# CLK_INPUT.net
KiCad netlist of a schematic drawn in Altium Designer
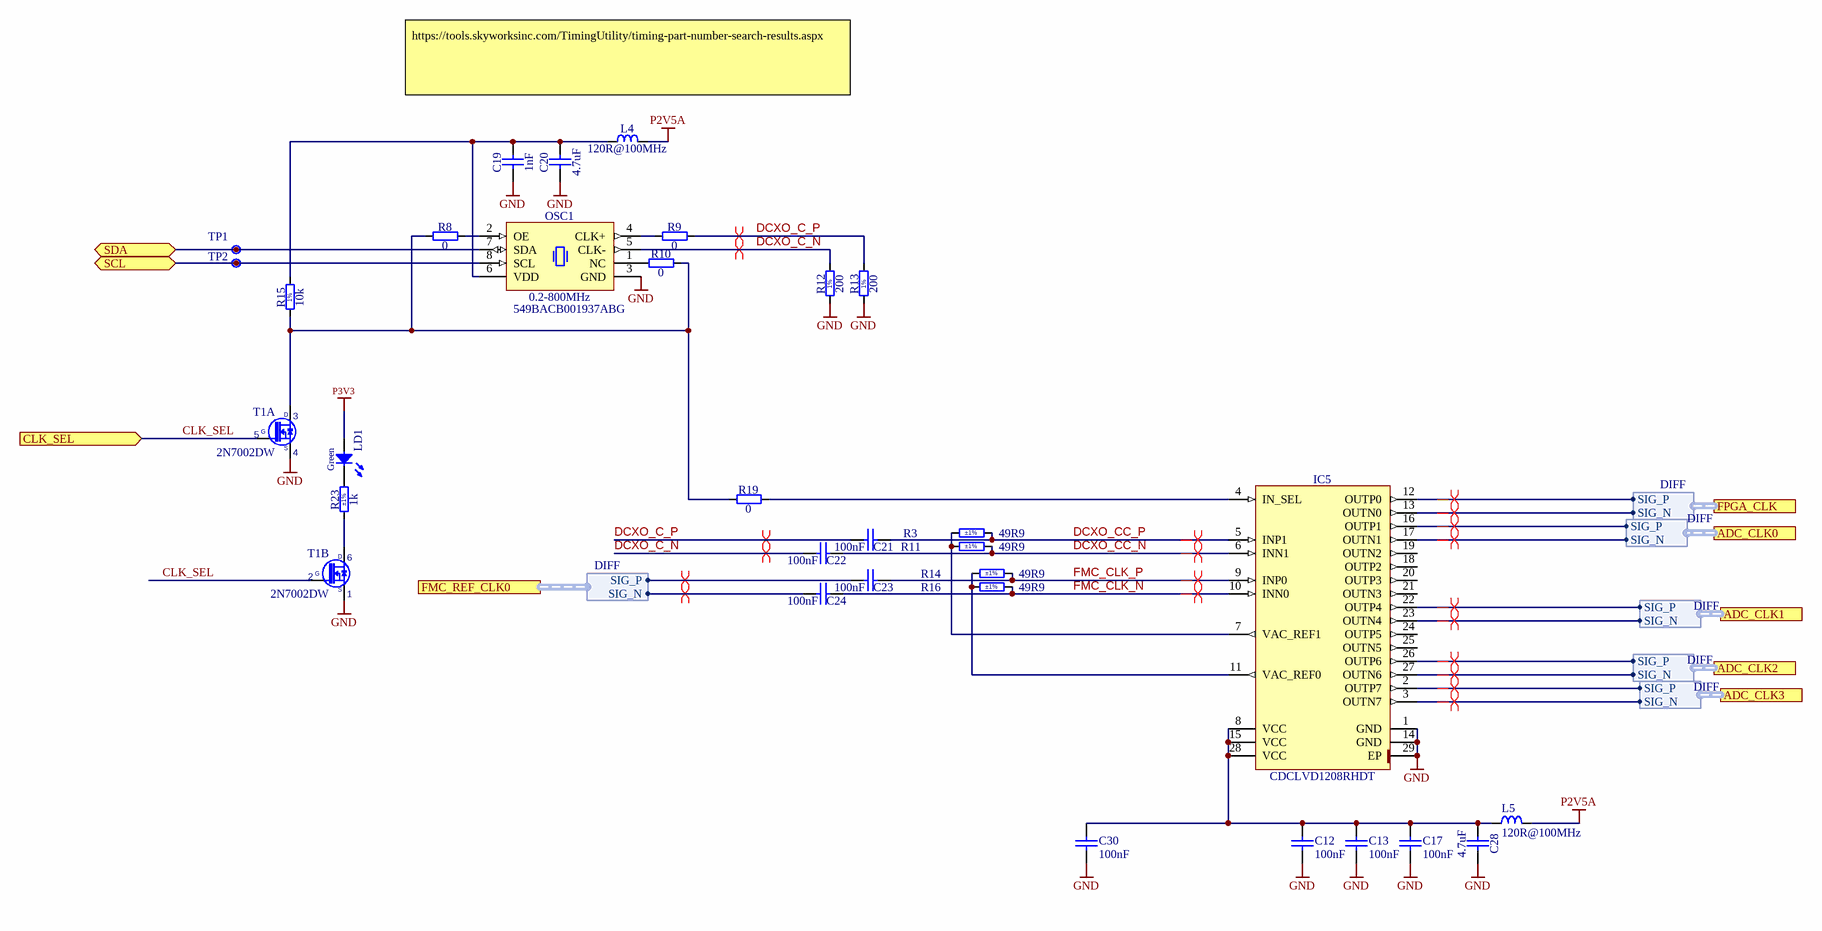
[diagram p0: CLK_INPUT.SchDoc]

(export (version "E")
  (design (tool "Eeschema 10.0.6"))
  (components
    (comp (ref "C12")
      (value "100nF")
      (footprint "CAPC0603X33N")
      (description "Non-polarised capacitor")
      (fields
        (field (name "PART NUMBER") "CC0201_100NF_6.3V_10%_X5R")
        (field (name "VOLTAGE") "6.3V")
        (field (name "AUTHOR") "CERN DEM JLC")
      )
      (libsource (lib "Capacitors") (part "Capacitor - non polarized"))
    )
    (comp (ref "C13")
      (value "100nF")
      (footprint "CAPC0603X33N")
      (description "Non-polarised capacitor")
      (fields
        (field (name "PART NUMBER") "CC0201_100NF_6.3V_10%_X5R")
        (field (name "VOLTAGE") "6.3V")
        (field (name "AUTHOR") "CERN DEM JLC")
      )
      (libsource (lib "Capacitors") (part "Capacitor - non polarized"))
    )
    (comp (ref "C17")
      (value "100nF")
      (footprint "CAPC0603X33N")
      (description "Non-polarised capacitor")
      (fields
        (field (name "PART NUMBER") "CC0201_100NF_6.3V_10%_X5R")
        (field (name "VOLTAGE") "6.3V")
        (field (name "AUTHOR") "CERN DEM JLC")
      )
      (libsource (lib "Capacitors") (part "Capacitor - non polarized"))
    )
    (comp (ref "C19")
      (value "1nF")
      (footprint "CAPC1005X55N")
      (description "Non-polarised capacitor")
      (fields
        (field (name "PART NUMBER") "CC0402_1NF_50V_10%_X7R")
        (field (name "VOLTAGE") "50V")
        (field (name "AUTHOR") "CERN DEM JLC")
      )
      (libsource (lib "Capacitors") (part "Capacitor - non polarized"))
    )
    (comp (ref "C20")
      (value "4.7uF")
      (footprint "CAPC2012X135N")
      (description "Non-polarised capacitor")
      (fields
        (field (name "PART NUMBER") "CC0805_4.7UF_10V_10%_X5R")
        (field (name "VOLTAGE") "10V")
        (field (name "AUTHOR") "CERN DEM JLC")
      )
      (libsource (lib "Capacitors") (part "Capacitor - non polarized"))
    )
    (comp (ref "C21")
      (value "100nF")
      (footprint "CAPC0603X33N")
      (description "Non-polarised capacitor")
      (fields
        (field (name "PART NUMBER") "CC0201_100NF_6.3V_10%_X5R")
        (field (name "VOLTAGE") "6.3V")
        (field (name "AUTHOR") "CERN DEM JLC")
      )
      (libsource (lib "Capacitors") (part "Capacitor - non polarized"))
    )
    (comp (ref "C22")
      (value "100nF")
      (footprint "CAPC0603X33N")
      (description "Non-polarised capacitor")
      (fields
        (field (name "PART NUMBER") "CC0201_100NF_6.3V_10%_X5R")
        (field (name "VOLTAGE") "6.3V")
        (field (name "AUTHOR") "CERN DEM JLC")
      )
      (libsource (lib "Capacitors") (part "Capacitor - non polarized"))
    )
    (comp (ref "C23")
      (value "100nF")
      (footprint "CAPC0603X33N")
      (description "Non-polarised capacitor")
      (fields
        (field (name "PART NUMBER") "CC0201_100NF_6.3V_10%_X5R")
        (field (name "VOLTAGE") "6.3V")
        (field (name "AUTHOR") "CERN DEM JLC")
      )
      (libsource (lib "Capacitors") (part "Capacitor - non polarized"))
    )
    (comp (ref "C24")
      (value "100nF")
      (footprint "CAPC0603X33N")
      (description "Non-polarised capacitor")
      (fields
        (field (name "PART NUMBER") "CC0201_100NF_6.3V_10%_X5R")
        (field (name "VOLTAGE") "6.3V")
        (field (name "AUTHOR") "CERN DEM JLC")
      )
      (libsource (lib "Capacitors") (part "Capacitor - non polarized"))
    )
    (comp (ref "C28")
      (value "4.7uF")
      (footprint "CAPC2012X135N")
      (description "Non-polarised capacitor")
      (fields
        (field (name "PART NUMBER") "CC0805_4.7UF_10V_10%_X5R")
        (field (name "VOLTAGE") "10V")
        (field (name "AUTHOR") "CERN DEM JLC")
      )
      (libsource (lib "Capacitors") (part "Capacitor - non polarized"))
    )
    (comp (ref "C30")
      (value "100nF")
      (footprint "CAPC0603X33N")
      (description "Non-polarised capacitor")
      (fields
        (field (name "PART NUMBER") "CC0201_100NF_6.3V_10%_X5R")
        (field (name "VOLTAGE") "6.3V")
        (field (name "AUTHOR") "CERN DEM JLC")
      )
      (libsource (lib "Capacitors") (part "Capacitor - non polarized"))
    )
    (comp (ref "IC5")
      (value "CDCLVD1208RHDT")
      (footprint "QFN50P500X500X100-29N-S325")
      (description "2:8 Low Additive Jitter LVDS Buffer")
      (fields (field (name "MANUFACTURER") "TEXAS INSTRUMENTS") (field (name "AUTHOR") "CERN DEM JLC"))
      (libsource (lib "ICs And Semiconductors") (part "CDCLVD1208"))
    )
    (comp (ref "L4")
      (value "120R@100MHz")
      (footprint "INDC1608X65N")
      (description "Inductor")
      (fields
        (field (name "PART NUMBER") "IND0603_MURATA_BLM18SG121TN1D")
        (field (name "POWER") "3A")
        (field (name "AUTHOR") "CERN DEM JLC")
      )
      (libsource (lib "") (part "Inductor_1"))
    )
    (comp (ref "L5")
      (value "120R@100MHz")
      (footprint "INDC1608X95N")
      (description "Inductor")
      (fields
        (field (name "PART NUMBER") "IND0603_MURATA_BLM18PG121SN1D")
        (field (name "POWER") "2A")
        (field (name "AUTHOR") "CERN DEM BC")
      )
      (libsource (lib "Inductors & Transformers") (part "Inductor"))
    )
    (comp (ref "LD1")
      (value "Green")
      (footprint "LED_KINGBRIGHT_KPA-1606CGCK")
      (description "LED Green 1C 2A")
      (fields
        (field (name "PART NUMBER") "LED_KINGBRIGHT_KPA-1606CGCK")
        (field (name "MANUFACTURER") "KINGBRIGHT")
        (field (name "AUTHOR") "CERN DEM MR")
      )
      (libsource (lib "ICs And Semiconductors") (part "LED Green 1C 2A"))
    )
    (comp (ref "OSC1")
      (value "0.2-800MHz")
      (footprint "OSC_SILICON-LAB_SI549-A")
      (description "Ultra Low Jitter I2C Programmable Crystal Oscillator (XO), Si549 Series")
      (fields
        (field (name "PART NUMBER") "OSC_0.2-800MHZ_SILICON-LAB_549BACB001937ABG")
        (field (name "MANUFACTURER") "SILICON LABS")
        (field (name "MANUFACTURER PART NUMBER") "549BACB001937ABG")
        (field (name "AUTHOR") "CERN DEM JMW")
      )
      (libsource (lib "ICs And Semiconductors") (part "Oscillator SILICON-LAB_Si549-CD"))
    )
    (comp (ref "R3")
      (value "49R9")
      (footprint "RESC1005X40N")
      (description "Resistor - 1%")
      (fields
        (field (name "TOLERANCE") "±1%")
        (field (name "PART NUMBER") "R0402_49R9_1%_0.0625W_100PPM")
        (field (name "POWER") "0.0625W")
        (field (name "AUTHOR") "CERN DEM JLC")
      )
      (libsource (lib "Resistors") (part "Resistor - 1%"))
    )
    (comp (ref "R8")
      (value "0")
      (footprint "RESC1005X40N")
      (description "Resistor")
      (fields
        (field (name "PART NUMBER") "R0402_0R_JUMPER")
        (field (name "MANUFACTURER") "GENERIC")
        (field (name "AUTHOR") "CERN DEM JLC")
      )
      (libsource (lib "Resistors") (part "Resistor"))
    )
    (comp (ref "R9")
      (value "0")
      (footprint "RESC1005X40N")
      (description "Resistor")
      (fields
        (field (name "PART NUMBER") "R0402_0R_JUMPER")
        (field (name "MANUFACTURER") "GENERIC")
        (field (name "AUTHOR") "CERN DEM JLC")
      )
      (libsource (lib "Resistors") (part "Resistor"))
    )
    (comp (ref "R10")
      (value "0")
      (footprint "RESC1005X40N")
      (description "Resistor")
      (fields
        (field (name "PART NUMBER") "R0402_0R_JUMPER")
        (field (name "MANUFACTURER") "GENERIC")
        (field (name "AUTHOR") "CERN DEM JLC")
      )
      (libsource (lib "Resistors") (part "Resistor"))
    )
    (comp (ref "R11")
      (value "49R9")
      (footprint "RESC1005X40N")
      (description "Resistor - 1%")
      (fields
        (field (name "TOLERANCE") "±1%")
        (field (name "PART NUMBER") "R0402_49R9_1%_0.0625W_100PPM")
        (field (name "POWER") "0.0625W")
        (field (name "AUTHOR") "CERN DEM JLC")
      )
      (libsource (lib "Resistors") (part "Resistor - 1%"))
    )
    (comp (ref "R12")
      (value "200")
      (footprint "RESC1005X40N")
      (description "Resistor - 1%")
      (fields
        (field (name "PART NUMBER") "R0402_200R_1%_0.0625W_100PPM")
        (field (name "POWER") "0.0625W")
        (field (name "AUTHOR") "CERN DEM JLC")
      )
      (libsource (lib "Resistors") (part "Resistor - 1%"))
    )
    (comp (ref "R13")
      (value "200")
      (footprint "RESC1005X40N")
      (description "Resistor - 1%")
      (fields
        (field (name "PART NUMBER") "R0402_200R_1%_0.0625W_100PPM")
        (field (name "POWER") "0.0625W")
        (field (name "AUTHOR") "CERN DEM JLC")
      )
      (libsource (lib "Resistors") (part "Resistor - 1%"))
    )
    (comp (ref "R14")
      (value "49R9")
      (footprint "RESC1005X40N")
      (description "Resistor - 1%")
      (fields
        (field (name "TOLERANCE") "±1%")
        (field (name "PART NUMBER") "R0402_49R9_1%_0.0625W_100PPM")
        (field (name "POWER") "0.0625W")
        (field (name "AUTHOR") "CERN DEM JLC")
      )
      (libsource (lib "Resistors") (part "Resistor - 1%"))
    )
    (comp (ref "R15")
      (value "10k")
      (footprint "RESC1005X40N")
      (description "Resistor - 1%")
      (fields
        (field (name "PART NUMBER") "R0402_10K_1%_0.0625W_100PPM")
        (field (name "POWER") "0.0625W")
        (field (name "AUTHOR") "CERN DEM JLC")
      )
      (libsource (lib "Resistors") (part "Resistor - 1%"))
    )
    (comp (ref "R16")
      (value "49R9")
      (footprint "RESC1005X40N")
      (description "Resistor - 1%")
      (fields
        (field (name "TOLERANCE") "±1%")
        (field (name "PART NUMBER") "R0402_49R9_1%_0.0625W_100PPM")
        (field (name "POWER") "0.0625W")
        (field (name "AUTHOR") "CERN DEM JLC")
      )
      (libsource (lib "Resistors") (part "Resistor - 1%"))
    )
    (comp (ref "R19")
      (value "0")
      (footprint "RESC1005X40N")
      (description "Resistor")
      (fields
        (field (name "PART NUMBER") "R0402_0R_JUMPER")
        (field (name "MANUFACTURER") "GENERIC")
        (field (name "AUTHOR") "CERN DEM JLC")
      )
      (libsource (lib "Resistors") (part "Resistor"))
    )
    (comp (ref "R23")
      (value "1k")
      (footprint "RESC1005X40N")
      (description "Resistor - 1%")
      (fields
        (field (name "TOLERANCE") "±1%")
        (field (name "PART NUMBER") "R0402_1K_1%_0.0625W_100PPM")
        (field (name "POWER") "0.0625W")
        (field (name "AUTHOR") "CERN DEM JLC")
      )
      (libsource (lib "Resistors") (part "Resistor - 1%"))
    )
    (comp (ref "T1")
      (value "2N7002DW")
      (footprint "SOT65P210X110-6N")
      (description "60 V, 115 mA, Dual N-Channel Field Effect Transistor, Enhancement Mode")
      (fields (field (name "MANUFACTURER") "ON SEMICONDUCTOR") (field (name "AUTHOR") "CERN DEM BC"))
      (libsource (lib "ICs And Semiconductors") (part "2N7002DW"))
    )
    (comp (ref "TP1")
      (value "I2C SW SDA")
      (footprint "TPS127")
      (description "Test Point")
      (fields (field (name "PART NUMBER") "SMD_PAD_1.27X1.27MM") (field (name "AUTHOR") "CERN DEM JLC"))
      (libsource (lib "Eletro-mechanical") (part "Test Point"))
    )
    (comp (ref "TP2")
      (value "I2C SW SCL")
      (footprint "TPS127")
      (description "Test Point")
      (fields (field (name "PART NUMBER") "SMD_PAD_1.27X1.27MM") (field (name "AUTHOR") "CERN DEM JLC"))
      (libsource (lib "Eletro-mechanical") (part "Test Point"))
    )
  )
  (nets
    (net (code "2") (name "/CLK_SEL") (class "Default")
      (node (ref "T1") (pin "2") (pinfunction "G2_2") (pintype "passive"))
      (node (ref "T1") (pin "5") (pinfunction "G1_5") (pintype "passive"))
    )
    (net (code "3") (name "/DCXO_CC_N") (class "Default")
      (node (ref "C22") (pin "2") (pinfunction "2_2") (pintype "passive"))
      (node (ref "IC5") (pin "6") (pinfunction "INN1_6") (pintype "input"))
      (node (ref "R11") (pin "2") (pinfunction "2_2") (pintype "passive"))
    )
    (net (code "4") (name "/DCXO_CC_P") (class "Default")
      (node (ref "C21") (pin "2") (pinfunction "2_2") (pintype "passive"))
      (node (ref "IC5") (pin "5") (pinfunction "INP1_5") (pintype "input"))
      (node (ref "R3") (pin "2") (pinfunction "2_2") (pintype "passive"))
    )
    (net (code "5") (name "/DCXO_C_N") (class "Default")
      (node (ref "C22") (pin "1") (pinfunction "1_1") (pintype "passive"))
      (node (ref "OSC1") (pin "5") (pinfunction "CLK-_5") (pintype "output"))
      (node (ref "R12") (pin "2") (pinfunction "2_2") (pintype "passive"))
    )
    (net (code "6") (name "/DCXO_C_P") (class "Default")
      (node (ref "C21") (pin "1") (pinfunction "1_1") (pintype "passive"))
      (node (ref "R13") (pin "2") (pinfunction "2_2") (pintype "passive"))
      (node (ref "R9") (pin "2") (pinfunction "2_2") (pintype "passive"))
    )
    (net (code "7") (name "/FMC_CLK_N") (class "Default")
      (node (ref "C24") (pin "2") (pinfunction "2_2") (pintype "passive"))
      (node (ref "IC5") (pin "10") (pinfunction "INN0_10") (pintype "input"))
      (node (ref "R16") (pin "2") (pinfunction "2_2") (pintype "passive"))
    )
    (net (code "8") (name "/FMC_CLK_P") (class "Default")
      (node (ref "C23") (pin "2") (pinfunction "2_2") (pintype "passive"))
      (node (ref "IC5") (pin "9") (pinfunction "INP0_9") (pintype "input"))
      (node (ref "R14") (pin "2") (pinfunction "2_2") (pintype "passive"))
    )
    (net (code "9") (name "/SCL") (class "Default")
      (node (ref "OSC1") (pin "8") (pinfunction "SCL_8") (pintype "input"))
      (node (ref "TP2") (pin "1") (pinfunction "1_1") (pintype "bidirectional"))
    )
    (net (code "10") (name "/SDA") (class "Default")
      (node (ref "OSC1") (pin "7") (pinfunction "SDA_7") (pintype "bidirectional"))
      (node (ref "TP1") (pin "1") (pinfunction "1_1") (pintype "bidirectional"))
    )
    (net (code "12") (name "GND") (class "Default")
      (node (ref "C12") (pin "1") (pinfunction "1_1") (pintype "passive"))
      (node (ref "C13") (pin "1") (pinfunction "1_1") (pintype "passive"))
      (node (ref "C17") (pin "1") (pinfunction "1_1") (pintype "passive"))
      (node (ref "C19") (pin "1") (pinfunction "1_1") (pintype "passive"))
      (node (ref "C20") (pin "1") (pinfunction "1_1") (pintype "passive"))
      (node (ref "C28") (pin "1") (pinfunction "1_1") (pintype "passive"))
      (node (ref "C30") (pin "1") (pinfunction "1_1") (pintype "passive"))
      (node (ref "IC5") (pin "1") (pinfunction "GND_1") (pintype "power_in"))
      (node (ref "IC5") (pin "14") (pinfunction "GND_14") (pintype "power_in"))
      (node (ref "IC5") (pin "29") (pinfunction "EP_29") (pintype "power_in"))
      (node (ref "OSC1") (pin "3") (pinfunction "GND_3") (pintype "power_in"))
      (node (ref "R12") (pin "1") (pinfunction "1_1") (pintype "passive"))
      (node (ref "R13") (pin "1") (pinfunction "1_1") (pintype "passive"))
      (node (ref "T1") (pin "1") (pinfunction "S2_1") (pintype "passive"))
      (node (ref "T1") (pin "4") (pinfunction "S1_4") (pintype "passive"))
    )
    (net (code "13") (name "Net-(C12-Pad2)") (class "Default")
      (node (ref "C12") (pin "2") (pinfunction "2_2") (pintype "passive"))
      (node (ref "C13") (pin "2") (pinfunction "2_2") (pintype "passive"))
      (node (ref "C17") (pin "2") (pinfunction "2_2") (pintype "passive"))
      (node (ref "C28") (pin "2") (pinfunction "2_2") (pintype "passive"))
      (node (ref "C30") (pin "2") (pinfunction "2_2") (pintype "passive"))
      (node (ref "IC5") (pin "15") (pinfunction "VCC_15") (pintype "power_in"))
      (node (ref "IC5") (pin "28") (pinfunction "VCC_28") (pintype "power_in"))
      (node (ref "IC5") (pin "8") (pinfunction "VCC_8") (pintype "power_in"))
      (node (ref "L5") (pin "1") (pinfunction "1_1") (pintype "passive"))
    )
    (net (code "14") (name "Net-(IC5-IN_SEL)") (class "Default")
      (node (ref "IC5") (pin "4") (pinfunction "IN_SEL_4") (pintype "input"))
      (node (ref "R19") (pin "2") (pinfunction "2_2") (pintype "passive"))
    )
    (net (code "15") (name "Net-(IC5-VAC_REF0)") (class "Default")
      (node (ref "IC5") (pin "11") (pinfunction "VAC_REF0_11") (pintype "output"))
      (node (ref "R14") (pin "1") (pinfunction "1_1") (pintype "passive"))
      (node (ref "R16") (pin "1") (pinfunction "1_1") (pintype "passive"))
    )
    (net (code "16") (name "Net-(IC5-VAC_REF1)") (class "Default")
      (node (ref "IC5") (pin "7") (pinfunction "VAC_REF1_7") (pintype "output"))
      (node (ref "R11") (pin "1") (pinfunction "1_1") (pintype "passive"))
      (node (ref "R3") (pin "1") (pinfunction "1_1") (pintype "passive"))
    )
    (net (code "17") (name "Net-(LD1-C)") (class "Default")
      (node (ref "LD1") (pin "1") (pinfunction "C_1") (pintype "passive"))
      (node (ref "R23") (pin "2") (pinfunction "2_2") (pintype "passive"))
    )
    (net (code "18") (name "Net-(OSC1-CLK+)") (class "Default")
      (node (ref "OSC1") (pin "4") (pinfunction "CLK+_4") (pintype "output"))
      (node (ref "R9") (pin "1") (pinfunction "1_1") (pintype "passive"))
    )
    (net (code "19") (name "Net-(OSC1-NC)") (class "Default")
      (node (ref "OSC1") (pin "1") (pinfunction "NC_1") (pintype "passive"))
      (node (ref "R10") (pin "1") (pinfunction "1_1") (pintype "passive"))
    )
    (net (code "20") (name "Net-(OSC1-OE)") (class "Default")
      (node (ref "OSC1") (pin "2") (pinfunction "OE_2") (pintype "input"))
      (node (ref "R8") (pin "2") (pinfunction "2_2") (pintype "passive"))
    )
    (net (code "21") (name "Net-(OSC1-VDD)") (class "Default")
      (node (ref "C19") (pin "2") (pinfunction "2_2") (pintype "passive"))
      (node (ref "C20") (pin "2") (pinfunction "2_2") (pintype "passive"))
      (node (ref "L4") (pin "2") (pinfunction "2_2") (pintype "passive"))
      (node (ref "OSC1") (pin "6") (pinfunction "VDD_6") (pintype "power_in"))
      (node (ref "R15") (pin "2") (pinfunction "2_2") (pintype "passive"))
    )
    (net (code "22") (name "Net-(T1A-D1)") (class "Default")
      (node (ref "R10") (pin "2") (pinfunction "2_2") (pintype "passive"))
      (node (ref "R15") (pin "1") (pinfunction "1_1") (pintype "passive"))
      (node (ref "R19") (pin "1") (pinfunction "1_1") (pintype "passive"))
      (node (ref "R8") (pin "1") (pinfunction "1_1") (pintype "passive"))
      (node (ref "T1") (pin "3") (pinfunction "D1_3") (pintype "passive"))
    )
    (net (code "23") (name "Net-(T1B-D2)") (class "Default")
      (node (ref "R23") (pin "1") (pinfunction "1_1") (pintype "passive"))
      (node (ref "T1") (pin "6") (pinfunction "D2_6") (pintype "passive"))
    )
    (net (code "24") (name "P2V5A") (class "Default")
      (node (ref "L4") (pin "1") (pinfunction "1_1") (pintype "passive"))
      (node (ref "L5") (pin "2") (pinfunction "2_2") (pintype "passive"))
    )
    (net (code "25") (name "P3V3") (class "Default")
      (node (ref "LD1") (pin "2") (pinfunction "A_2") (pintype "passive"))
    )
    (net (code "26") (name "unconnected-(C23-Pad1)") (class "Default")
      (node (ref "C23") (pin "1") (pinfunction "1_1") (pintype "passive"))
    )
    (net (code "27") (name "unconnected-(C24-Pad1)") (class "Default")
      (node (ref "C24") (pin "1") (pinfunction "1_1") (pintype "passive"))
    )
    (net (code "28") (name "unconnected-(IC5-OUTN0-Pad13)") (class "Default")
      (node (ref "IC5") (pin "13") (pinfunction "OUTN0_13") (pintype "output"))
    )
    (net (code "29") (name "unconnected-(IC5-OUTN1-Pad17)") (class "Default")
      (node (ref "IC5") (pin "17") (pinfunction "OUTN1_17") (pintype "output"))
    )
    (net (code "30") (name "unconnected-(IC5-OUTN2-Pad19)") (class "Default")
      (node (ref "IC5") (pin "19") (pinfunction "OUTN2_19") (pintype "output"))
    )
    (net (code "31") (name "unconnected-(IC5-OUTN3-Pad21)") (class "Default")
      (node (ref "IC5") (pin "21") (pinfunction "OUTN3_21") (pintype "output"))
    )
    (net (code "32") (name "unconnected-(IC5-OUTN4-Pad23)") (class "Default")
      (node (ref "IC5") (pin "23") (pinfunction "OUTN4_23") (pintype "output"))
    )
    (net (code "33") (name "unconnected-(IC5-OUTN5-Pad25)") (class "Default")
      (node (ref "IC5") (pin "25") (pinfunction "OUTN5_25") (pintype "output"))
    )
    (net (code "34") (name "unconnected-(IC5-OUTN6-Pad27)") (class "Default")
      (node (ref "IC5") (pin "27") (pinfunction "OUTN6_27") (pintype "output"))
    )
    (net (code "35") (name "unconnected-(IC5-OUTN7-Pad3)") (class "Default")
      (node (ref "IC5") (pin "3") (pinfunction "OUTN7_3") (pintype "output"))
    )
    (net (code "36") (name "unconnected-(IC5-OUTP0-Pad12)") (class "Default")
      (node (ref "IC5") (pin "12") (pinfunction "OUTP0_12") (pintype "output"))
    )
    (net (code "37") (name "unconnected-(IC5-OUTP1-Pad16)") (class "Default")
      (node (ref "IC5") (pin "16") (pinfunction "OUTP1_16") (pintype "output"))
    )
    (net (code "38") (name "unconnected-(IC5-OUTP2-Pad18)") (class "Default")
      (node (ref "IC5") (pin "18") (pinfunction "OUTP2_18") (pintype "output"))
    )
    (net (code "39") (name "unconnected-(IC5-OUTP3-Pad20)") (class "Default")
      (node (ref "IC5") (pin "20") (pinfunction "OUTP3_20") (pintype "output"))
    )
    (net (code "40") (name "unconnected-(IC5-OUTP4-Pad22)") (class "Default")
      (node (ref "IC5") (pin "22") (pinfunction "OUTP4_22") (pintype "output"))
    )
    (net (code "41") (name "unconnected-(IC5-OUTP5-Pad24)") (class "Default")
      (node (ref "IC5") (pin "24") (pinfunction "OUTP5_24") (pintype "output"))
    )
    (net (code "42") (name "unconnected-(IC5-OUTP6-Pad26)") (class "Default")
      (node (ref "IC5") (pin "26") (pinfunction "OUTP6_26") (pintype "output"))
    )
    (net (code "43") (name "unconnected-(IC5-OUTP7-Pad2)") (class "Default")
      (node (ref "IC5") (pin "2") (pinfunction "OUTP7_2") (pintype "output"))
    )
  )
)
